# dimmerPower9.net
KiCad netlist of a schematic drawn in EAGLE
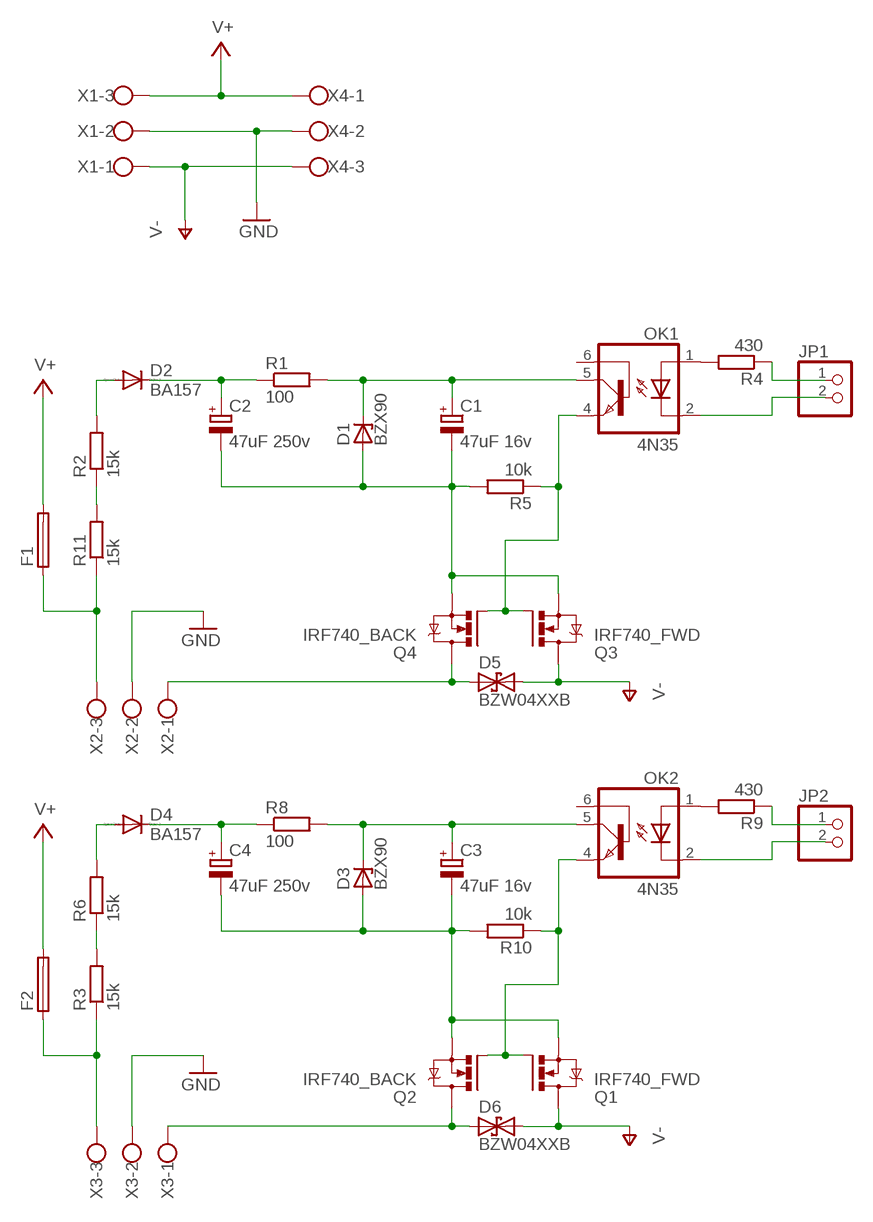
[diagram p0: schematic, sheet 1]

(export (version "E")
  (design (tool "Eeschema 10.0.6"))
  (components
    (comp (ref "C1")
      (value "47uF 16v")
      (footprint "eagle-import:E2,5-6")
      (libsource (lib "eagle-import") (part "CPOL-EUE2.5-6"))
    )
    (comp (ref "C2")
      (value "47uF 250v")
      (footprint "eagle-import:E5-13")
      (libsource (lib "eagle-import") (part "CPOL-EUE5-13"))
    )
    (comp (ref "C3")
      (value "47uF 16v")
      (footprint "eagle-import:E2,5-6")
      (libsource (lib "eagle-import") (part "CPOL-EUE2.5-6"))
    )
    (comp (ref "C4")
      (value "47uF 250v")
      (footprint "eagle-import:E5-13")
      (libsource (lib "eagle-import") (part "CPOL-EUE5-13"))
    )
    (comp (ref "D1")
      (value "BZX90")
      (footprint "eagle-import:DO34Z7")
      (libsource (lib "eagle-import") (part "BZX90"))
    )
    (comp (ref "D2")
      (value "BA157")
      (footprint "eagle-import:P1-10")
      (libsource (lib "eagle-import") (part "BA157"))
    )
    (comp (ref "D3")
      (value "BZX90")
      (footprint "eagle-import:DO34Z7")
      (libsource (lib "eagle-import") (part "BZX90"))
    )
    (comp (ref "D4")
      (value "BA157")
      (footprint "eagle-import:P1-10")
      (libsource (lib "eagle-import") (part "BA157"))
    )
    (comp (ref "D5")
      (value "BZW04XXB")
      (footprint "eagle-import:F126Z12")
      (libsource (lib "eagle-import") (part "BZW04XXB"))
    )
    (comp (ref "D6")
      (value "BZW04XXB")
      (footprint "eagle-import:F126Z12")
      (libsource (lib "eagle-import") (part "BZW04XXB"))
    )
    (comp (ref "F1")
      (value "SH22,5")
      (footprint "eagle-import:SH22,5")
      (fields (field (name "MF") "SCHURTER") (field (name "MPN") "0031.8201"))
      (libsource (lib "eagle-import") (part "SH22,5"))
    )
    (comp (ref "F2")
      (value "SH22,5")
      (footprint "eagle-import:SH22,5")
      (fields (field (name "MF") "SCHURTER") (field (name "MPN") "0031.8201"))
      (libsource (lib "eagle-import") (part "SH22,5"))
    )
    (comp (ref "JP1")
      (value "PINHD-1X2")
      (footprint "eagle-import:1X02")
      (libsource (lib "eagle-import") (part "PINHD-1X2"))
    )
    (comp (ref "JP2")
      (value "PINHD-1X2")
      (footprint "eagle-import:1X02")
      (libsource (lib "eagle-import") (part "PINHD-1X2"))
    )
    (comp (ref "OK1")
      (value "4N35")
      (footprint "eagle-import:DIL06")
      (fields (field (name "MF") "FAIRCHILD SEMICONDUCTOR"))
      (libsource (lib "eagle-import") (part "4N35"))
    )
    (comp (ref "OK2")
      (value "4N35")
      (footprint "eagle-import:DIL06")
      (fields (field (name "MF") "FAIRCHILD SEMICONDUCTOR"))
      (libsource (lib "eagle-import") (part "4N35"))
    )
    (comp (ref "Q1")
      (value "IRF740_FWD")
      (footprint "eagle-import:TO220BV_FWD")
      (libsource (lib "eagle-import") (part "IRF740_FWD"))
    )
    (comp (ref "Q2")
      (value "IRF740_BACK")
      (footprint "eagle-import:TO220BV_BACK")
      (libsource (lib "eagle-import") (part "IRF740_BACK"))
    )
    (comp (ref "Q3")
      (value "IRF740_FWD")
      (footprint "eagle-import:TO220BV_FWD")
      (libsource (lib "eagle-import") (part "IRF740_FWD"))
    )
    (comp (ref "Q4")
      (value "IRF740_BACK")
      (footprint "eagle-import:TO220BV_BACK")
      (libsource (lib "eagle-import") (part "IRF740_BACK"))
    )
    (comp (ref "R1")
      (value "100")
      (footprint "eagle-import:0204_7")
      (libsource (lib "eagle-import") (part "R-EU_0204/7"))
    )
    (comp (ref "R2")
      (value "15k")
      (footprint "eagle-import:P0613_15")
      (libsource (lib "eagle-import") (part "untitled_R-EU_0613/15"))
    )
    (comp (ref "R3")
      (value "15k")
      (footprint "eagle-import:P0613_15")
      (libsource (lib "eagle-import") (part "untitled_R-EU_0613/15"))
    )
    (comp (ref "R4")
      (value "430")
      (footprint "eagle-import:0204_7")
      (libsource (lib "eagle-import") (part "R-EU_0204/7"))
    )
    (comp (ref "R5")
      (value "10k")
      (footprint "eagle-import:0204_7")
      (libsource (lib "eagle-import") (part "R-EU_0204/7"))
    )
    (comp (ref "R6")
      (value "15k")
      (footprint "eagle-import:P0613_15")
      (libsource (lib "eagle-import") (part "untitled_R-EU_0613/15"))
    )
    (comp (ref "R8")
      (value "100")
      (footprint "eagle-import:0204_7")
      (libsource (lib "eagle-import") (part "R-EU_0204/7"))
    )
    (comp (ref "R9")
      (value "430")
      (footprint "eagle-import:0204_7")
      (libsource (lib "eagle-import") (part "R-EU_0204/7"))
    )
    (comp (ref "R10")
      (value "10k")
      (footprint "eagle-import:0204_7")
      (libsource (lib "eagle-import") (part "R-EU_0204/7"))
    )
    (comp (ref "R11")
      (value "15k")
      (footprint "eagle-import:P0613_15")
      (libsource (lib "eagle-import") (part "untitled_R-EU_0613/15"))
    )
    (comp (ref "X1")
      (value "W237-103")
      (footprint "eagle-import:W237-103")
      (fields (field (name "MPN") "237-103"))
      (libsource (lib "eagle-import") (part "W237-103"))
    )
    (comp (ref "X2")
      (value "W237-103")
      (footprint "eagle-import:W237-103")
      (fields (field (name "MPN") "237-103"))
      (libsource (lib "eagle-import") (part "W237-103"))
    )
    (comp (ref "X3")
      (value "W237-103")
      (footprint "eagle-import:W237-103")
      (fields (field (name "MPN") "237-103"))
      (libsource (lib "eagle-import") (part "W237-103"))
    )
    (comp (ref "X4")
      (value "W237-103")
      (footprint "eagle-import:W237-103")
      (fields (field (name "MPN") "237-103"))
      (libsource (lib "eagle-import") (part "W237-103"))
    )
  )
  (nets
    (net (code "1") (name "GND") (class "Default")
      (node (ref "X1") (pin "2") (pinfunction "KL_2") (pintype "passive"))
      (node (ref "X2") (pin "2") (pinfunction "KL_2") (pintype "passive"))
      (node (ref "X3") (pin "2") (pinfunction "KL_2") (pintype "passive"))
      (node (ref "X4") (pin "2") (pinfunction "KL_2") (pintype "passive"))
    )
    (net (code "2") (name "Net-(C1-Pad-)") (class "Default")
      (node (ref "C1") (pin "-") (pinfunction "-_-") (pintype "passive"))
      (node (ref "C2") (pin "-") (pinfunction "-_-") (pintype "passive"))
      (node (ref "D1") (pin "A") (pinfunction "A_A") (pintype "passive"))
      (node (ref "Q3") (pin "S") (pinfunction "S_S") (pintype "passive"))
      (node (ref "Q4") (pin "S") (pinfunction "S_S") (pintype "passive"))
      (node (ref "R5") (pin "2") (pinfunction "2_2") (pintype "passive"))
    )
    (net (code "3") (name "Net-(C2-Pad+)") (class "Default")
      (node (ref "C2") (pin "+") (pinfunction "+_+") (pintype "passive"))
      (node (ref "D2") (pin "C") (pinfunction "C_C") (pintype "passive"))
      (node (ref "R1") (pin "1") (pinfunction "1_1") (pintype "passive"))
    )
    (net (code "4") (name "Net-(C3-Pad-)") (class "Default")
      (node (ref "C3") (pin "-") (pinfunction "-_-") (pintype "passive"))
      (node (ref "C4") (pin "-") (pinfunction "-_-") (pintype "passive"))
      (node (ref "D3") (pin "A") (pinfunction "A_A") (pintype "passive"))
      (node (ref "Q1") (pin "S") (pinfunction "S_S") (pintype "passive"))
      (node (ref "Q2") (pin "S") (pinfunction "S_S") (pintype "passive"))
      (node (ref "R10") (pin "2") (pinfunction "2_2") (pintype "passive"))
    )
    (net (code "5") (name "Net-(C4-Pad+)") (class "Default")
      (node (ref "C4") (pin "+") (pinfunction "+_+") (pintype "passive"))
      (node (ref "D4") (pin "C") (pinfunction "C_C") (pintype "passive"))
      (node (ref "R8") (pin "1") (pinfunction "1_1") (pintype "passive"))
    )
    (net (code "6") (name "Net-(D2-PadA)") (class "Default")
      (node (ref "D2") (pin "A") (pinfunction "A_A") (pintype "passive"))
      (node (ref "R2") (pin "2") (pinfunction "2_2") (pintype "passive"))
    )
    (net (code "7") (name "Net-(D4-PadA)") (class "Default")
      (node (ref "D4") (pin "A") (pinfunction "A_A") (pintype "passive"))
      (node (ref "R6") (pin "2") (pinfunction "2_2") (pintype "passive"))
    )
    (net (code "8") (name "Net-(D5-1)") (class "Default")
      (node (ref "D5") (pin "A") (pinfunction "1_A") (pintype "passive"))
      (node (ref "Q4") (pin "D") (pinfunction "D_D") (pintype "passive"))
      (node (ref "X2") (pin "1") (pinfunction "KL_1") (pintype "passive"))
    )
    (net (code "9") (name "Net-(D6-1)") (class "Default")
      (node (ref "D6") (pin "A") (pinfunction "1_A") (pintype "passive"))
      (node (ref "Q2") (pin "D") (pinfunction "D_D") (pintype "passive"))
      (node (ref "X3") (pin "1") (pinfunction "KL_1") (pintype "passive"))
    )
    (net (code "10") (name "Net-(JP1-Pad1)") (class "Default")
      (node (ref "JP1") (pin "1") (pinfunction "1_1") (pintype "passive"))
      (node (ref "R4") (pin "1") (pinfunction "1_1") (pintype "passive"))
    )
    (net (code "11") (name "Net-(JP2-Pad1)") (class "Default")
      (node (ref "JP2") (pin "1") (pinfunction "1_1") (pintype "passive"))
      (node (ref "R9") (pin "1") (pinfunction "1_1") (pintype "passive"))
    )
    (net (code "12") (name "Net-(OK1-A)") (class "Default")
      (node (ref "OK1") (pin "1") (pinfunction "A_1") (pintype "passive"))
      (node (ref "R4") (pin "2") (pinfunction "2_2") (pintype "passive"))
    )
    (net (code "13") (name "Net-(OK1-C)") (class "Default")
      (node (ref "JP1") (pin "2") (pinfunction "2_2") (pintype "passive"))
      (node (ref "OK1") (pin "2") (pinfunction "C_2") (pintype "passive"))
    )
    (net (code "14") (name "Net-(OK1-COL)") (class "Default")
      (node (ref "C1") (pin "+") (pinfunction "+_+") (pintype "passive"))
      (node (ref "D1") (pin "C") (pinfunction "C_C") (pintype "passive"))
      (node (ref "OK1") (pin "5") (pinfunction "COL_5") (pintype "passive"))
      (node (ref "R1") (pin "2") (pinfunction "2_2") (pintype "passive"))
    )
    (net (code "15") (name "Net-(OK1-EMI)") (class "Default")
      (node (ref "OK1") (pin "4") (pinfunction "EMI_4") (pintype "passive"))
      (node (ref "Q3") (pin "G") (pinfunction "G_G") (pintype "passive"))
      (node (ref "Q4") (pin "G") (pinfunction "G_G") (pintype "passive"))
      (node (ref "R5") (pin "1") (pinfunction "1_1") (pintype "passive"))
    )
    (net (code "16") (name "Net-(OK2-A)") (class "Default")
      (node (ref "OK2") (pin "1") (pinfunction "A_1") (pintype "passive"))
      (node (ref "R9") (pin "2") (pinfunction "2_2") (pintype "passive"))
    )
    (net (code "17") (name "Net-(OK2-C)") (class "Default")
      (node (ref "JP2") (pin "2") (pinfunction "2_2") (pintype "passive"))
      (node (ref "OK2") (pin "2") (pinfunction "C_2") (pintype "passive"))
    )
    (net (code "18") (name "Net-(OK2-COL)") (class "Default")
      (node (ref "C3") (pin "+") (pinfunction "+_+") (pintype "passive"))
      (node (ref "D3") (pin "C") (pinfunction "C_C") (pintype "passive"))
      (node (ref "OK2") (pin "5") (pinfunction "COL_5") (pintype "passive"))
      (node (ref "R8") (pin "2") (pinfunction "2_2") (pintype "passive"))
    )
    (net (code "19") (name "Net-(OK2-EMI)") (class "Default")
      (node (ref "OK2") (pin "4") (pinfunction "EMI_4") (pintype "passive"))
      (node (ref "Q1") (pin "G") (pinfunction "G_G") (pintype "passive"))
      (node (ref "Q2") (pin "G") (pinfunction "G_G") (pintype "passive"))
      (node (ref "R10") (pin "1") (pinfunction "1_1") (pintype "passive"))
    )
    (net (code "20") (name "Net-(R3-Pad2)") (class "Default")
      (node (ref "R3") (pin "2") (pinfunction "2_2") (pintype "passive"))
      (node (ref "R6") (pin "1") (pinfunction "1_1") (pintype "passive"))
    )
    (net (code "21") (name "Net-(R11-Pad2)") (class "Default")
      (node (ref "R11") (pin "2") (pinfunction "2_2") (pintype "passive"))
      (node (ref "R2") (pin "1") (pinfunction "1_1") (pintype "passive"))
    )
    (net (code "22") (name "Net-(X2C-KL)") (class "Default")
      (node (ref "F1") (pin "1") (pinfunction "1_1") (pintype "passive"))
      (node (ref "R11") (pin "1") (pinfunction "1_1") (pintype "passive"))
      (node (ref "X2") (pin "3") (pinfunction "KL_3") (pintype "passive"))
    )
    (net (code "23") (name "Net-(X3C-KL)") (class "Default")
      (node (ref "F2") (pin "1") (pinfunction "1_1") (pintype "passive"))
      (node (ref "R3") (pin "1") (pinfunction "1_1") (pintype "passive"))
      (node (ref "X3") (pin "3") (pinfunction "KL_3") (pintype "passive"))
    )
    (net (code "24") (name "V+") (class "Default")
      (node (ref "F1") (pin "2") (pinfunction "2_2") (pintype "passive"))
      (node (ref "F2") (pin "2") (pinfunction "2_2") (pintype "passive"))
      (node (ref "X1") (pin "3") (pinfunction "KL_3") (pintype "passive"))
      (node (ref "X4") (pin "1") (pinfunction "KL_1") (pintype "passive"))
    )
    (net (code "25") (name "V-") (class "Default")
      (node (ref "D5") (pin "C") (pinfunction "2_C") (pintype "passive"))
      (node (ref "D6") (pin "C") (pinfunction "2_C") (pintype "passive"))
      (node (ref "Q1") (pin "D") (pinfunction "D_D") (pintype "passive"))
      (node (ref "Q3") (pin "D") (pinfunction "D_D") (pintype "passive"))
      (node (ref "X1") (pin "1") (pinfunction "KL_1") (pintype "passive"))
      (node (ref "X4") (pin "3") (pinfunction "KL_3") (pintype "passive"))
    )
    (net (code "26") (name "unconnected-(OK1-BAS-Pad6)") (class "Default")
      (node (ref "OK1") (pin "6") (pinfunction "BAS_6") (pintype "passive"))
    )
    (net (code "27") (name "unconnected-(OK2-BAS-Pad6)") (class "Default")
      (node (ref "OK2") (pin "6") (pinfunction "BAS_6") (pintype "passive"))
    )
  )
)
